# Main_sheet.net
KiCad netlist of a schematic drawn in Altium Designer
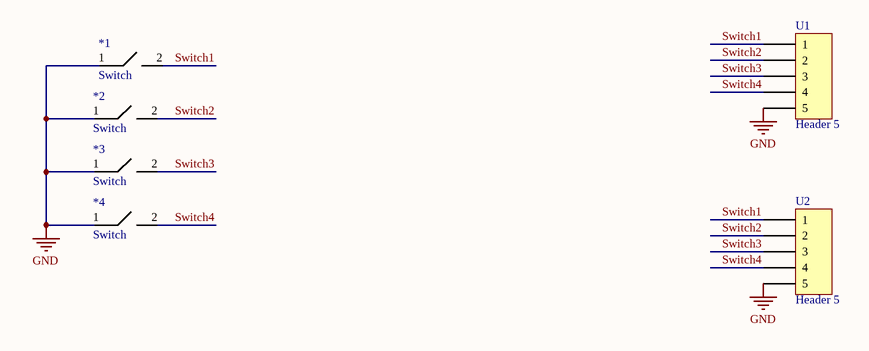
[diagram p0: Main sheet.SchDoc]

(export (version "E")
  (design (tool "Eeschema 10.0.6"))
  (components
    (comp (ref "*1") (value "Switch") (footprint "Switch") (libsource (lib "AlexChistiakov") (part "Switch")))
    (comp (ref "*2") (value "Switch") (footprint "Switch") (libsource (lib "AlexChistiakov") (part "Switch")))
    (comp (ref "*3") (value "Switch") (footprint "Switch") (libsource (lib "AlexChistiakov") (part "Switch")))
    (comp (ref "*4") (value "Switch") (footprint "Switch") (libsource (lib "AlexChistiakov") (part "Switch")))
    (comp (ref "U1")
      (value "Header 5")
      (footprint "5x1.27")
      (libsource (lib "AlexChistiakov") (part "Header 5"))
    )
    (comp (ref "U2")
      (value "Header 5")
      (footprint "5x2.54")
      (libsource (lib "AlexChistiakov") (part "Header 5"))
    )
  )
  (nets
    (net (code "1") (name "/Switch1") (class "Default")
      (node (ref "*1") (pin "2") (pinfunction "2_2") (pintype "passive"))
      (node (ref "U1") (pin "1") (pinfunction "1_1") (pintype "power_in"))
      (node (ref "U2") (pin "1") (pinfunction "1_1") (pintype "power_in"))
    )
    (net (code "2") (name "/Switch2") (class "Default")
      (node (ref "*2") (pin "2") (pinfunction "2_2") (pintype "passive"))
      (node (ref "U1") (pin "2") (pinfunction "2_2") (pintype "power_in"))
      (node (ref "U2") (pin "2") (pinfunction "2_2") (pintype "power_in"))
    )
    (net (code "3") (name "/Switch3") (class "Default")
      (node (ref "*3") (pin "2") (pinfunction "2_2") (pintype "passive"))
      (node (ref "U1") (pin "3") (pinfunction "3_3") (pintype "power_in"))
      (node (ref "U2") (pin "3") (pinfunction "3_3") (pintype "power_in"))
    )
    (net (code "4") (name "/Switch4") (class "Default")
      (node (ref "*4") (pin "2") (pinfunction "2_2") (pintype "passive"))
      (node (ref "U1") (pin "4") (pinfunction "4_4") (pintype "power_in"))
      (node (ref "U2") (pin "4") (pinfunction "4_4") (pintype "power_in"))
    )
    (net (code "5") (name "GND") (class "Default")
      (node (ref "*1") (pin "1") (pinfunction "1_1") (pintype "passive"))
      (node (ref "*2") (pin "1") (pinfunction "1_1") (pintype "passive"))
      (node (ref "*3") (pin "1") (pinfunction "1_1") (pintype "passive"))
      (node (ref "*4") (pin "1") (pinfunction "1_1") (pintype "passive"))
      (node (ref "U1") (pin "5") (pinfunction "5_5") (pintype "power_in"))
      (node (ref "U2") (pin "5") (pinfunction "5_5") (pintype "power_in"))
    )
  )
)
